# encoder.net
KiCad netlist of a schematic drawn in EAGLE
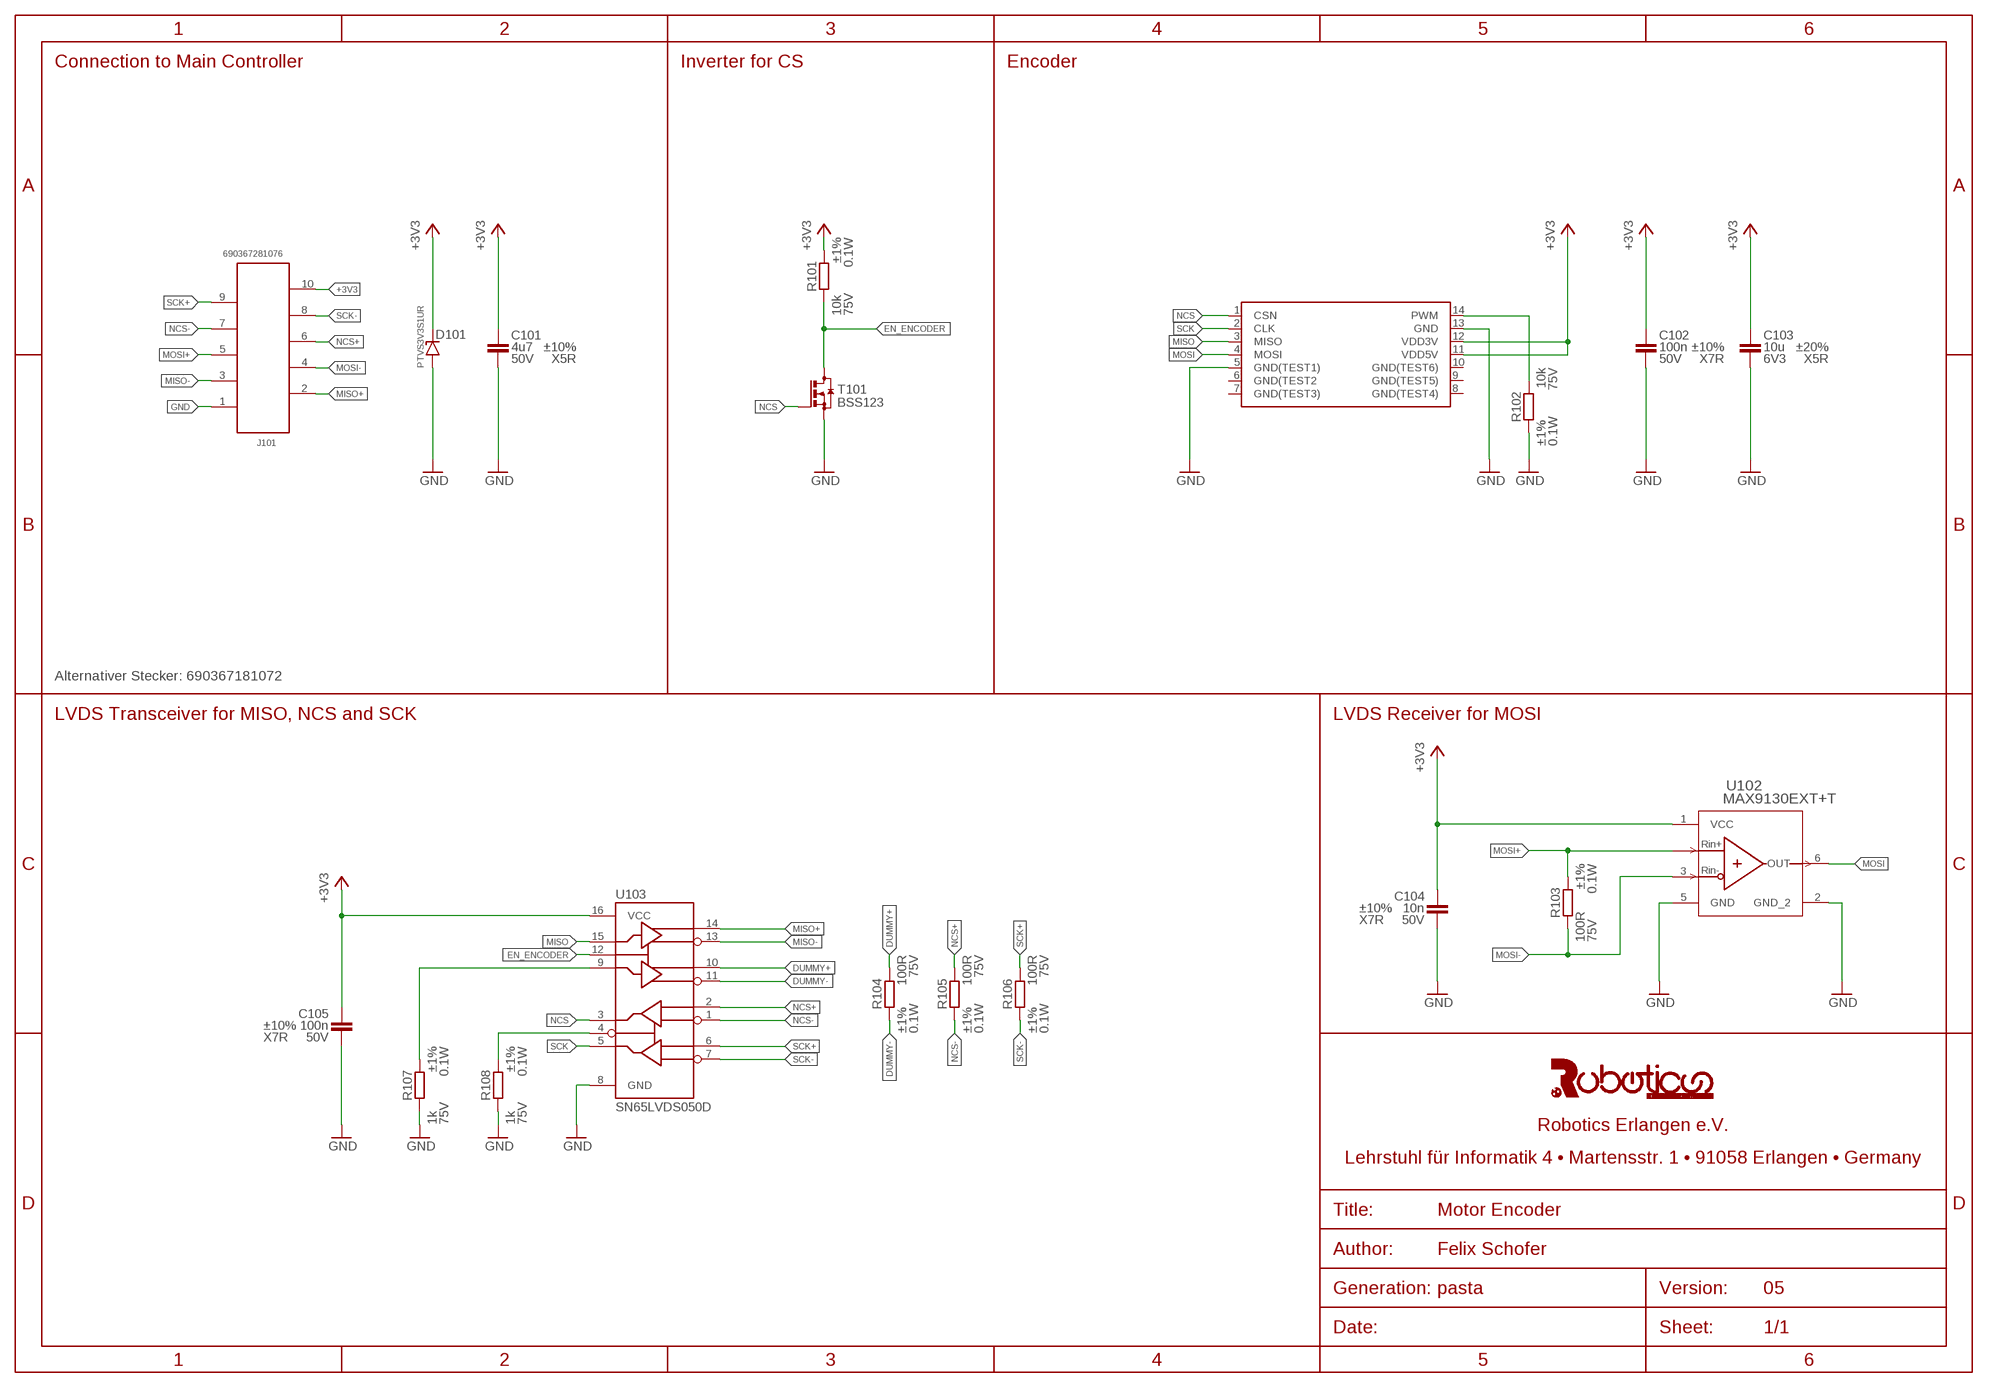
[diagram p0: schematic, sheet 1]

(export (version "E")
  (design (tool "Eeschema 10.0.6"))
  (components
    (comp (ref "C101")
      (value "4u7 6V3")
      (footprint "eagle-import:C0805")
      (fields
        (field (name "CAPACITANCE") "4u7")
        (field (name "DIELECTRIC") "X5R")
        (field (name "MF") "Samsung")
        (field (name "MPN") "CL21A475KBQNNNE")
        (field (name "TOLERANCE") "±10%")
        (field (name "VOLTAGE") "50V")
      )
      (libsource (lib "eagle-import") (part "C(?)08054.7UF,50V,"))
    )
    (comp (ref "C102")
      (value "100n 6V3")
      (footprint "eagle-import:C0603")
      (fields
        (field (name "CAPACITANCE") "100n")
        (field (name "DIELECTRIC") "X7R")
        (field (name "MF") "Würth Elektronik")
        (field (name "MPN") "885012206095")
        (field (name "TOLERANCE") "±10%")
        (field (name "VOLTAGE") "50V")
      )
      (libsource (lib "eagle-import") (part "C(?)0603100NF,50V,"))
    )
    (comp (ref "C103")
      (value "10u 6V3")
      (footprint "eagle-import:C0603")
      (fields
        (field (name "CAPACITANCE") "10u")
        (field (name "DIELECTRIC") "X5R")
        (field (name "MF") "Würth Elektronik")
        (field (name "MPN") "885012106006")
        (field (name "TOLERANCE") "±20%")
        (field (name "VOLTAGE") "6V3")
      )
      (libsource (lib "eagle-import") (part "C(?)060310UF,6.3V,"))
    )
    (comp (ref "C104")
      (value "10n 50V")
      (footprint "eagle-import:C0603")
      (fields
        (field (name "CAPACITANCE") "10n")
        (field (name "DIELECTRIC") "X7R")
        (field (name "MF") "Würth Elektronik")
        (field (name "MPN") "885012206089")
        (field (name "TOLERANCE") "±10%")
        (field (name "VOLTAGE") "50V")
      )
      (libsource (lib "eagle-import") (part "C(?)060310NF,50V,"))
    )
    (comp (ref "C105")
      (value "100n 6V3")
      (footprint "eagle-import:C0603")
      (fields
        (field (name "CAPACITANCE") "100n")
        (field (name "DIELECTRIC") "X7R")
        (field (name "MF") "Würth Elektronik")
        (field (name "MPN") "885012206095")
        (field (name "TOLERANCE") "±10%")
        (field (name "VOLTAGE") "50V")
      )
      (libsource (lib "eagle-import") (part "C(?)0603100NF,50V,"))
    )
    (comp (ref "D101")
      (value "PTVS3V3S1UR")
      (footprint "eagle-import:SOD123")
      (fields
        (field (name "MF") "Nexperia")
        (field (name "MPN") " PTVS3V3S1UR,115")
        (field (name "MF_1") "Nexperia")
      )
      (libsource (lib "eagle-import") (part "PTVSS1UR3V3"))
    )
    (comp (ref "J101")
      (value "690367281076")
      (footprint "eagle-import:690367281076")
      (fields (field (name "MF") "Würth Elektronik") (field (name "MPN") "690367281076"))
      (libsource (lib "eagle-import") (part "690367281076"))
    )
    (comp (ref "R101")
      (value "10k")
      (footprint "eagle-import:R0603")
      (fields
        (field (name "MF") "YAGEO")
        (field (name "MPN") "RC0603FR-0710KL")
        (field (name "POWER") "0.1W")
        (field (name "RESISTANCE") "10k")
        (field (name "TOLERANCE") "±1%")
        (field (name "VOLTAGE") "75V")
      )
      (libsource (lib "eagle-import") (part "R(?)060310K,75V,0.1W,"))
    )
    (comp (ref "R102")
      (value "10k")
      (footprint "eagle-import:R0603")
      (fields
        (field (name "MF") "YAGEO")
        (field (name "MPN") "RC0603FR-0710KL")
        (field (name "POWER") "0.1W")
        (field (name "RESISTANCE") "10k")
        (field (name "TOLERANCE") "±1%")
        (field (name "VOLTAGE") "75V")
      )
      (libsource (lib "eagle-import") (part "R(?)060310K,75V,0.1W,"))
    )
    (comp (ref "R103")
      (value "100R")
      (footprint "eagle-import:R0603")
      (fields
        (field (name "MF") "YAGEO")
        (field (name "MPN") "RC0603FR-07100RL")
        (field (name "POWER") "0.1W")
        (field (name "RESISTANCE") "100R")
        (field (name "TOLERANCE") "±1%")
        (field (name "VOLTAGE") "75V")
      )
      (libsource (lib "eagle-import") (part "R(?)0603100R,75V,0.1W,"))
    )
    (comp (ref "R104")
      (value "100R")
      (footprint "eagle-import:R0603")
      (fields
        (field (name "MF") "YAGEO")
        (field (name "MPN") "RC0603FR-07100RL")
        (field (name "POWER") "0.1W")
        (field (name "RESISTANCE") "100R")
        (field (name "TOLERANCE") "±1%")
        (field (name "VOLTAGE") "75V")
      )
      (libsource (lib "eagle-import") (part "R(?)0603100R,75V,0.1W,"))
    )
    (comp (ref "R105")
      (value "100R")
      (footprint "eagle-import:R0603")
      (fields
        (field (name "MF") "YAGEO")
        (field (name "MPN") "RC0603FR-07100RL")
        (field (name "POWER") "0.1W")
        (field (name "RESISTANCE") "100R")
        (field (name "TOLERANCE") "±1%")
        (field (name "VOLTAGE") "75V")
      )
      (libsource (lib "eagle-import") (part "R(?)0603100R,75V,0.1W,"))
    )
    (comp (ref "R106")
      (value "100R")
      (footprint "eagle-import:R0603")
      (fields
        (field (name "MF") "YAGEO")
        (field (name "MPN") "RC0603FR-07100RL")
        (field (name "POWER") "0.1W")
        (field (name "RESISTANCE") "100R")
        (field (name "TOLERANCE") "±1%")
        (field (name "VOLTAGE") "75V")
      )
      (libsource (lib "eagle-import") (part "R(?)0603100R,75V,0.1W,"))
    )
    (comp (ref "R107")
      (value "1k")
      (footprint "eagle-import:R0603")
      (fields
        (field (name "MF") "YAGEO")
        (field (name "MPN") "RC0603FR-071KL")
        (field (name "POWER") "0.1W")
        (field (name "RESISTANCE") "1k")
        (field (name "TOLERANCE") "±1%")
        (field (name "VOLTAGE") "75V")
      )
      (libsource (lib "eagle-import") (part "R(?)06031.0K,75V,0.1W,"))
    )
    (comp (ref "R108")
      (value "1k")
      (footprint "eagle-import:R0603")
      (fields
        (field (name "MF") "YAGEO")
        (field (name "MPN") "RC0603FR-071KL")
        (field (name "POWER") "0.1W")
        (field (name "RESISTANCE") "1k")
        (field (name "TOLERANCE") "±1%")
        (field (name "VOLTAGE") "75V")
      )
      (libsource (lib "eagle-import") (part "R(?)06031.0K,75V,0.1W,"))
    )
    (comp (ref "T101")
      (value "BSS123")
      (footprint "eagle-import:SOT23-3")
      (fields (field (name "MF") "Nexperia") (field (name "MPN") "BSS123NH6327XTSA1"))
      (libsource (lib "eagle-import") (part "BSS123"))
    )
    (comp (ref "U101")
      (value "AS5048A-HTSP")
      (footprint "eagle-import:AS5048A-HTSP")
      (fields (field (name "MF") "ams"))
      (libsource (lib "eagle-import") (part "AS5048A-HTSP"))
    )
    (comp (ref "U102")
      (value "MAX9130EXT+T")
      (footprint "eagle-import:21-0077G_MXM")
      (fields
        (field (name "MF") "Maxim Integrated Products")
        (field (name "COPYRIGHT") "Copyright (C) 2021 Ultra Librarian. All rights reserved.")
      )
      (libsource (lib "eagle-import") (part "MAX9130EXT+T"))
    )
    (comp (ref "U103")
      (value "SN65LVDS050D")
      (footprint "eagle-import:SOIC-16")
      (fields (field (name "MF") "Texas Instruments"))
      (libsource (lib "eagle-import") (part "SN65LVDS050?D"))
    )
  )
  (nets
    (net (code "1") (name "+3V3") (class "Default")
      (node (ref "C101") (pin "1") (pinfunction "1_1") (pintype "passive"))
      (node (ref "C102") (pin "1") (pinfunction "1_1") (pintype "passive"))
      (node (ref "C103") (pin "1") (pinfunction "1_1") (pintype "passive"))
      (node (ref "C104") (pin "1") (pinfunction "1_1") (pintype "passive"))
      (node (ref "C105") (pin "1") (pinfunction "1_1") (pintype "passive"))
      (node (ref "D101") (pin "C") (pinfunction "KATHODE_C") (pintype "bidirectional"))
      (node (ref "J101") (pin "10") (pinfunction "1_10") (pintype "passive"))
      (node (ref "R101") (pin "2") (pinfunction "2_2") (pintype "passive"))
      (node (ref "U101") (pin "11") (pinfunction "VDD5V_11") (pintype "bidirectional"))
      (node (ref "U101") (pin "12") (pinfunction "VDD3V_12") (pintype "bidirectional"))
      (node (ref "U102") (pin "1") (pinfunction "VCC_1") (pintype "power_in"))
      (node (ref "U103") (pin "16") (pinfunction "VCC_16") (pintype "bidirectional"))
    )
    (net (code "2") (name "DUMMY+") (class "Default")
      (node (ref "R104") (pin "1") (pinfunction "1_1") (pintype "passive"))
      (node (ref "U103") (pin "10") (pinfunction "2Y_10") (pintype "bidirectional"))
    )
    (net (code "3") (name "DUMMY-") (class "Default")
      (node (ref "R104") (pin "2") (pinfunction "2_2") (pintype "passive"))
      (node (ref "U103") (pin "11") (pinfunction "2Z_11") (pintype "bidirectional"))
    )
    (net (code "4") (name "EN_ENCODER") (class "Default")
      (node (ref "R101") (pin "1") (pinfunction "1_1") (pintype "passive"))
      (node (ref "T101") (pin "3") (pinfunction "D_3") (pintype "passive"))
      (node (ref "U103") (pin "12") (pinfunction "DE_12") (pintype "bidirectional"))
    )
    (net (code "5") (name "GND") (class "Default")
      (node (ref "C101") (pin "2") (pinfunction "2_2") (pintype "passive"))
      (node (ref "C102") (pin "2") (pinfunction "2_2") (pintype "passive"))
      (node (ref "C103") (pin "2") (pinfunction "2_2") (pintype "passive"))
      (node (ref "C104") (pin "2") (pinfunction "2_2") (pintype "passive"))
      (node (ref "C105") (pin "2") (pinfunction "2_2") (pintype "passive"))
      (node (ref "D101") (pin "A") (pinfunction "ANODE_A") (pintype "bidirectional"))
      (node (ref "J101") (pin "1") (pinfunction "10_1") (pintype "passive"))
      (node (ref "R102") (pin "2") (pinfunction "2_2") (pintype "passive"))
      (node (ref "R107") (pin "1") (pinfunction "1_1") (pintype "passive"))
      (node (ref "R108") (pin "1") (pinfunction "1_1") (pintype "passive"))
      (node (ref "T101") (pin "2") (pinfunction "S_2") (pintype "passive"))
      (node (ref "U101") (pin "13") (pinfunction "GND_13") (pintype "bidirectional"))
      (node (ref "U101") (pin "5") (pinfunction "GND(TEST1)_5") (pintype "bidirectional"))
      (node (ref "U102") (pin "2") (pinfunction "GND_2_2") (pintype "power_in"))
      (node (ref "U102") (pin "5") (pinfunction "GND_5") (pintype "power_in"))
      (node (ref "U103") (pin "8") (pinfunction "GND_8") (pintype "bidirectional"))
    )
    (net (code "6") (name "MISO") (class "Default")
      (node (ref "U101") (pin "3") (pinfunction "MISO_3") (pintype "bidirectional"))
      (node (ref "U103") (pin "15") (pinfunction "1D_15") (pintype "bidirectional"))
    )
    (net (code "7") (name "MISO+") (class "Default")
      (node (ref "J101") (pin "2") (pinfunction "9_2") (pintype "passive"))
      (node (ref "U103") (pin "14") (pinfunction "1Y_14") (pintype "bidirectional"))
    )
    (net (code "8") (name "MISO-") (class "Default")
      (node (ref "J101") (pin "3") (pinfunction "8_3") (pintype "passive"))
      (node (ref "U103") (pin "13") (pinfunction "1Z_13") (pintype "bidirectional"))
    )
    (net (code "9") (name "MOSI") (class "Default")
      (node (ref "U101") (pin "4") (pinfunction "MOSI_4") (pintype "bidirectional"))
      (node (ref "U102") (pin "6") (pinfunction "OUT_6") (pintype "output"))
    )
    (net (code "10") (name "MOSI+") (class "Default")
      (node (ref "J101") (pin "5") (pinfunction "6_5") (pintype "passive"))
      (node (ref "R103") (pin "2") (pinfunction "2_2") (pintype "passive"))
      (node (ref "U102") (pin "4") (pinfunction "IN+_4") (pintype "input"))
    )
    (net (code "11") (name "MOSI-") (class "Default")
      (node (ref "J101") (pin "4") (pinfunction "7_4") (pintype "passive"))
      (node (ref "R103") (pin "1") (pinfunction "1_1") (pintype "passive"))
      (node (ref "U102") (pin "3") (pinfunction "IN-_3") (pintype "input"))
    )
    (net (code "12") (name "NCS") (class "Default")
      (node (ref "T101") (pin "1") (pinfunction "G_1") (pintype "passive"))
      (node (ref "U101") (pin "1") (pinfunction "CSN_1") (pintype "bidirectional"))
      (node (ref "U103") (pin "3") (pinfunction "1R_3") (pintype "bidirectional"))
    )
    (net (code "13") (name "NCS+") (class "Default")
      (node (ref "J101") (pin "6") (pinfunction "5_6") (pintype "passive"))
      (node (ref "R105") (pin "1") (pinfunction "1_1") (pintype "passive"))
      (node (ref "U103") (pin "2") (pinfunction "1A_2") (pintype "bidirectional"))
    )
    (net (code "14") (name "NCS-") (class "Default")
      (node (ref "J101") (pin "7") (pinfunction "4_7") (pintype "passive"))
      (node (ref "R105") (pin "2") (pinfunction "2_2") (pintype "passive"))
      (node (ref "U103") (pin "1") (pinfunction "1B_1") (pintype "bidirectional"))
    )
    (net (code "15") (name "Net-(U101-PWM)") (class "Default")
      (node (ref "R102") (pin "1") (pinfunction "1_1") (pintype "passive"))
      (node (ref "U101") (pin "14") (pinfunction "PWM_14") (pintype "bidirectional"))
    )
    (net (code "16") (name "Net-(U103-2D)") (class "Default")
      (node (ref "R107") (pin "2") (pinfunction "2_2") (pintype "passive"))
      (node (ref "U103") (pin "9") (pinfunction "2D_9") (pintype "bidirectional"))
    )
    (net (code "17") (name "Net-(U103-RE)") (class "Default")
      (node (ref "R108") (pin "2") (pinfunction "2_2") (pintype "passive"))
      (node (ref "U103") (pin "4") (pinfunction "RE_4") (pintype "bidirectional"))
    )
    (net (code "18") (name "SCK") (class "Default")
      (node (ref "U101") (pin "2") (pinfunction "CLK_2") (pintype "bidirectional"))
      (node (ref "U103") (pin "5") (pinfunction "2R_5") (pintype "bidirectional"))
    )
    (net (code "19") (name "SCK+") (class "Default")
      (node (ref "J101") (pin "9") (pinfunction "2_9") (pintype "passive"))
      (node (ref "R106") (pin "1") (pinfunction "1_1") (pintype "passive"))
      (node (ref "U103") (pin "6") (pinfunction "2A_6") (pintype "bidirectional"))
    )
    (net (code "20") (name "SCK-") (class "Default")
      (node (ref "J101") (pin "8") (pinfunction "3_8") (pintype "passive"))
      (node (ref "R106") (pin "2") (pinfunction "2_2") (pintype "passive"))
      (node (ref "U103") (pin "7") (pinfunction "2B_7") (pintype "bidirectional"))
    )
    (net (code "21") (name "unconnected-(U101-GND(TEST2-Pad6)") (class "Default")
      (node (ref "U101") (pin "6") (pinfunction "GND(TEST2_6") (pintype "bidirectional"))
    )
    (net (code "22") (name "unconnected-(U101-GND(TEST3)-Pad7)") (class "Default")
      (node (ref "U101") (pin "7") (pinfunction "GND(TEST3)_7") (pintype "bidirectional"))
    )
    (net (code "23") (name "unconnected-(U101-GND(TEST4)-Pad8)") (class "Default")
      (node (ref "U101") (pin "8") (pinfunction "GND(TEST4)_8") (pintype "bidirectional"))
    )
    (net (code "24") (name "unconnected-(U101-GND(TEST5)-Pad9)") (class "Default")
      (node (ref "U101") (pin "9") (pinfunction "GND(TEST5)_9") (pintype "bidirectional"))
    )
    (net (code "25") (name "unconnected-(U101-GND(TEST6)-Pad10)") (class "Default")
      (node (ref "U101") (pin "10") (pinfunction "GND(TEST6)_10") (pintype "bidirectional"))
    )
  )
)
